# Power.net
KiCad netlist of a schematic drawn in Altium Designer
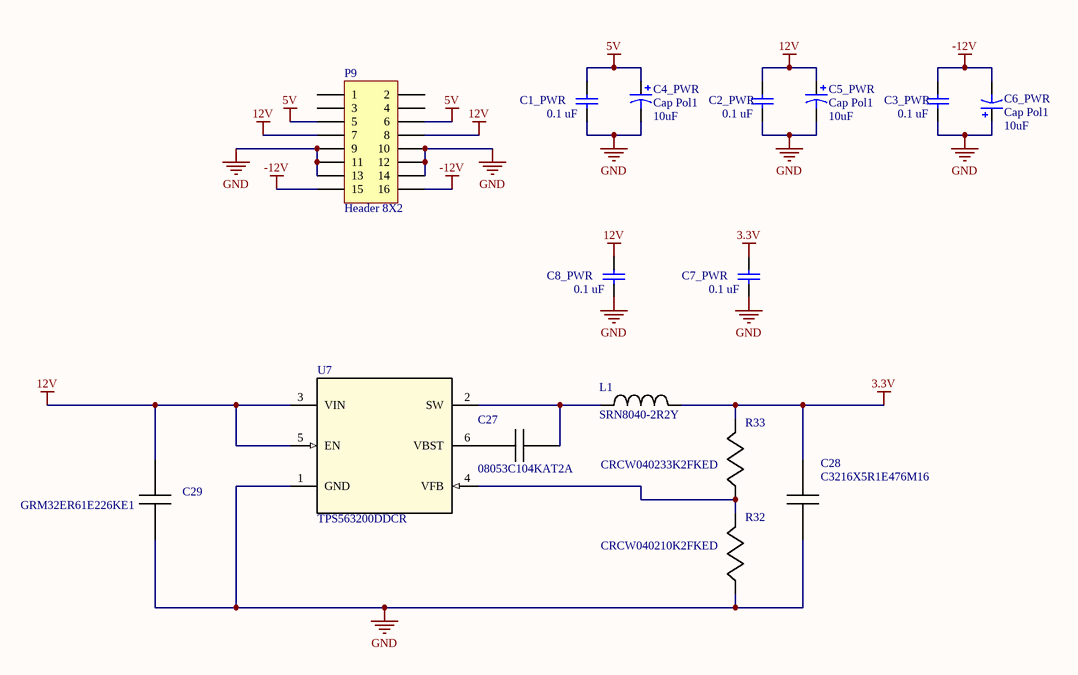
[diagram p0: Power.SchDoc]

(export (version "E")
  (design (tool "Eeschema 10.0.6"))
  (components
    (comp (ref "C1_PWR")
      (value "0.1 uF")
      (footprint "C0805")
      (description "Capacitor")
      (fields (field (name "PUBLISHER") "Altium Limited"))
      (libsource (lib "Miscellaneous Devices") (part "Cap"))
    )
    (comp (ref "C2_PWR")
      (value "0.1 uF")
      (footprint "C0805")
      (description "Capacitor")
      (fields (field (name "PUBLISHER") "Altium Limited"))
      (libsource (lib "Miscellaneous Devices") (part "Cap"))
    )
    (comp (ref "C3_PWR")
      (value "0.1 uF")
      (footprint "C0805")
      (description "Capacitor")
      (fields (field (name "PUBLISHER") "Altium Limited"))
      (libsource (lib "Miscellaneous Devices") (part "Cap"))
    )
    (comp (ref "C4_PWR")
      (value "Cap Pol1")
      (footprint "RB7.6-15")
      (description "Polarized Capacitor (Radial)")
      (fields (field (name "ALTIUM_VALUE") "10uF") (field (name "PUBLISHER") "Altium Limited"))
      (libsource (lib "Miscellaneous Devices") (part "Cap Pol1"))
    )
    (comp (ref "C5_PWR")
      (value "Cap Pol1")
      (footprint "RB7.6-15")
      (description "Polarized Capacitor (Radial)")
      (fields (field (name "ALTIUM_VALUE") "10uF") (field (name "PUBLISHER") "Altium Limited"))
      (libsource (lib "Miscellaneous Devices") (part "Cap Pol1"))
    )
    (comp (ref "C6_PWR")
      (value "Cap Pol1")
      (footprint "RB7.6-15")
      (description "Polarized Capacitor (Radial)")
      (fields (field (name "ALTIUM_VALUE") "10uF") (field (name "PUBLISHER") "Altium Limited"))
      (libsource (lib "Miscellaneous Devices") (part "Cap Pol1"))
    )
    (comp (ref "C7_PWR")
      (value "0.1 uF")
      (footprint "C0805")
      (description "Capacitor")
      (fields (field (name "PUBLISHER") "Altium Limited"))
      (libsource (lib "Miscellaneous Devices") (part "Cap"))
    )
    (comp (ref "C8_PWR")
      (value "0.1 uF")
      (footprint "C0805")
      (description "Capacitor")
      (fields (field (name "PUBLISHER") "Altium Limited"))
      (libsource (lib "Miscellaneous Devices") (part "Cap"))
    )
    (comp (ref "C27")
      (value "08053C104KAT2A")
      (footprint "0805")
      (description "Imported")
      (libsource (lib "2017-10-30_10-27-00") (part "08053C104KAT2A"))
    )
    (comp (ref "C28")
      (value "C3216X5R1E476M16")
      (footprint "1206")
      (description "Imported")
      (fields (field (name "MANUFACTURER_PART_NUMBER") "C3216X5R1E476M160AC"))
      (libsource (lib "2017-10-30_10-27-00") (part "C3216X5R1E476M16"))
    )
    (comp (ref "C29")
      (value "GRM32ER61E226KE1")
      (footprint "1210")
      (description "Imported")
      (fields (field (name "MANUFACTURER_PART_NUMBER") "GRM32ER61E226KE15L"))
      (libsource (lib "2017-10-30_10-27-00") (part "GRM32ER61E226KE1"))
    )
    (comp (ref "L1")
      (value "SRN8040-2R2Y")
      (footprint "SRN8040")
      (description "Imported")
      (libsource (lib "2017-10-03_20-29-25") (part "SRN8040-2R2Y"))
    )
    (comp (ref "P9")
      (value "Header 8X2")
      (footprint "HDR2X8")
      (description "Header, 8-Pin, Dual row")
      (fields (field (name "PUBLISHER") "Altium Limited"))
      (libsource (lib "Miscellaneous Connectors") (part "Header 8X2"))
    )
    (comp (ref "R32")
      (value "CRCW040210K2FKED")
      (footprint "0402")
      (description "Imported")
      (libsource (lib "2017-10-30_10-27-00") (part "CRCW040210K2FKED"))
    )
    (comp (ref "R33")
      (value "CRCW040233K2FKED")
      (footprint "0402")
      (description "Imported")
      (libsource (lib "2017-10-30_10-27-00") (part "CRCW040233K2FKED"))
    )
    (comp (ref "U7")
      (value "TPS563200DDCR")
      (footprint "DDC0006A")
      (description "Imported")
      (fields
        (field (name "PARTNUMBER") "TPS563200DDC")
        (field (name "MANUFACTURER") "Texas Instruments")
        (field (name "MODIFIEDDATE") "Not shown in title block")
        (field (name "APPROVEDBY") "Not shown in title block")
        (field (name "CHECKEDBY") "Not shown in title block")
        (field (name "AUTHOR") "Not shown in title block")
        (field (name "ENGINEER") "Not shown in title block")
        (field (name "SYMBOLCREATOR") "a0411947")
        (field (name "PUBLISHER") "Texas Instruments")
      )
      (libsource (lib "2017-10-03_20-29-25") (part "TPS563200DDCR"))
    )
  )
  (nets
    (net (code "1") (name "-12V") (class "Default")
      (node (ref "C3_PWR") (pin "2") (pinfunction "2_2") (pintype "passive"))
      (node (ref "C6_PWR") (pin "2") (pinfunction "2_2") (pintype "passive"))
      (node (ref "P9") (pin "15") (pinfunction "15_15") (pintype "passive"))
      (node (ref "P9") (pin "16") (pinfunction "16_16") (pintype "passive"))
    )
    (net (code "2") (name "3.3V") (class "Default")
      (node (ref "C28") (pin "1") (pinfunction "1_1") (pintype "passive"))
      (node (ref "C7_PWR") (pin "2") (pinfunction "2_2") (pintype "passive"))
      (node (ref "L1") (pin "2") (pinfunction "2_2") (pintype "passive"))
      (node (ref "R33") (pin "1") (pinfunction "1_1") (pintype "passive"))
    )
    (net (code "3") (name "5V") (class "Default")
      (node (ref "C1_PWR") (pin "2") (pinfunction "2_2") (pintype "passive"))
      (node (ref "C4_PWR") (pin "1") (pinfunction "1_1") (pintype "passive"))
      (node (ref "P9") (pin "5") (pinfunction "5_5") (pintype "passive"))
      (node (ref "P9") (pin "6") (pinfunction "6_6") (pintype "passive"))
    )
    (net (code "4") (name "12V") (class "Default")
      (node (ref "C29") (pin "1") (pinfunction "1_1") (pintype "passive"))
      (node (ref "C2_PWR") (pin "2") (pinfunction "2_2") (pintype "passive"))
      (node (ref "C5_PWR") (pin "1") (pinfunction "1_1") (pintype "passive"))
      (node (ref "C8_PWR") (pin "2") (pinfunction "2_2") (pintype "passive"))
      (node (ref "P9") (pin "7") (pinfunction "7_7") (pintype "passive"))
      (node (ref "P9") (pin "8") (pinfunction "8_8") (pintype "passive"))
      (node (ref "U7") (pin "3") (pinfunction "VIN_3") (pintype "power_in"))
      (node (ref "U7") (pin "5") (pinfunction "EN_5") (pintype "input"))
    )
    (net (code "5") (name "GND") (class "Default")
      (node (ref "C1_PWR") (pin "1") (pinfunction "1_1") (pintype "passive"))
      (node (ref "C28") (pin "2") (pinfunction "2_2") (pintype "passive"))
      (node (ref "C29") (pin "2") (pinfunction "2_2") (pintype "passive"))
      (node (ref "C2_PWR") (pin "1") (pinfunction "1_1") (pintype "passive"))
      (node (ref "C3_PWR") (pin "1") (pinfunction "1_1") (pintype "passive"))
      (node (ref "C4_PWR") (pin "2") (pinfunction "2_2") (pintype "passive"))
      (node (ref "C5_PWR") (pin "2") (pinfunction "2_2") (pintype "passive"))
      (node (ref "C6_PWR") (pin "1") (pinfunction "1_1") (pintype "passive"))
      (node (ref "C7_PWR") (pin "1") (pinfunction "1_1") (pintype "passive"))
      (node (ref "C8_PWR") (pin "1") (pinfunction "1_1") (pintype "passive"))
      (node (ref "P9") (pin "10") (pinfunction "10_10") (pintype "passive"))
      (node (ref "P9") (pin "11") (pinfunction "11_11") (pintype "passive"))
      (node (ref "P9") (pin "12") (pinfunction "12_12") (pintype "passive"))
      (node (ref "P9") (pin "13") (pinfunction "13_13") (pintype "passive"))
      (node (ref "P9") (pin "14") (pinfunction "14_14") (pintype "passive"))
      (node (ref "P9") (pin "9") (pinfunction "9_9") (pintype "passive"))
      (node (ref "R32") (pin "2") (pinfunction "2_2") (pintype "passive"))
      (node (ref "U7") (pin "1") (pinfunction "GND_1") (pintype "power_in"))
    )
    (net (code "6") (name "Net-(U7-SW)") (class "Default")
      (node (ref "C27") (pin "1") (pinfunction "1_1") (pintype "passive"))
      (node (ref "L1") (pin "1") (pinfunction "1_1") (pintype "passive"))
      (node (ref "U7") (pin "2") (pinfunction "SW_2") (pintype "power_in"))
    )
    (net (code "7") (name "Net-(U7-VBST)") (class "Default")
      (node (ref "C27") (pin "2") (pinfunction "2_2") (pintype "passive"))
      (node (ref "U7") (pin "6") (pinfunction "VBST_6") (pintype "power_in"))
    )
    (net (code "8") (name "Net-(U7-VFB)") (class "Default")
      (node (ref "R32") (pin "1") (pinfunction "1_1") (pintype "passive"))
      (node (ref "R33") (pin "2") (pinfunction "2_2") (pintype "passive"))
      (node (ref "U7") (pin "4") (pinfunction "VFB_4") (pintype "input"))
    )
    (net (code "9") (name "unconnected-(P9-Pad1)") (class "Default")
      (node (ref "P9") (pin "1") (pinfunction "1_1") (pintype "passive"))
    )
    (net (code "10") (name "unconnected-(P9-Pad2)") (class "Default")
      (node (ref "P9") (pin "2") (pinfunction "2_2") (pintype "passive"))
    )
    (net (code "11") (name "unconnected-(P9-Pad3)") (class "Default")
      (node (ref "P9") (pin "3") (pinfunction "3_3") (pintype "passive"))
    )
    (net (code "12") (name "unconnected-(P9-Pad4)") (class "Default")
      (node (ref "P9") (pin "4") (pinfunction "4_4") (pintype "passive"))
    )
  )
)
